# hw2_pcb.net
KiCad netlist of a schematic drawn in EAGLE
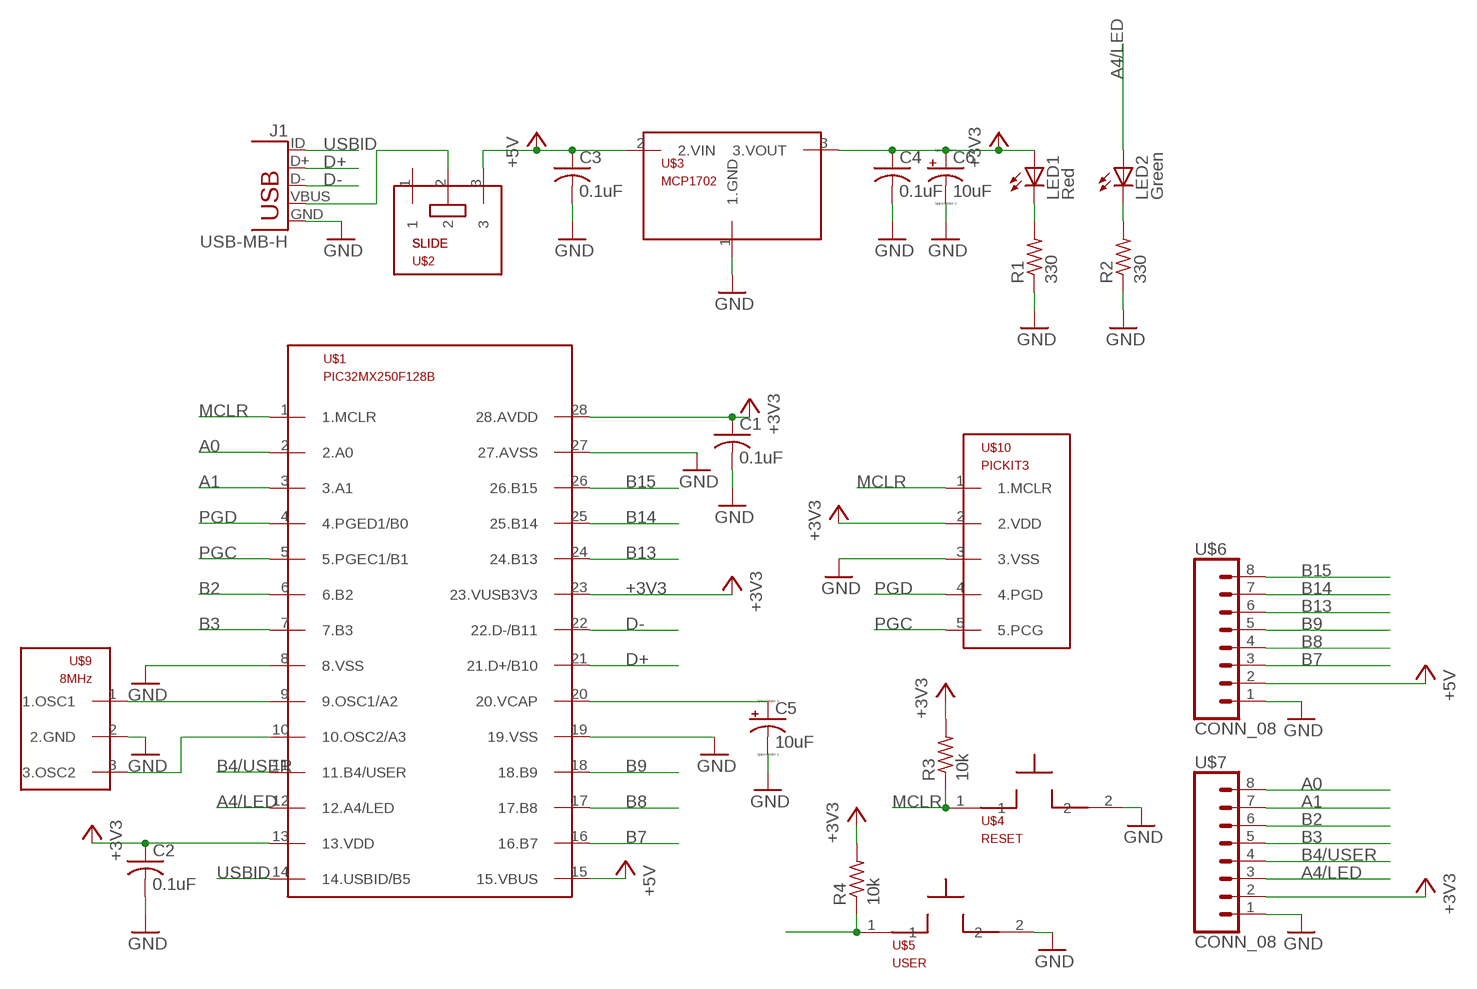
[diagram p0: schematic, sheet 1]

(export (version "E")
  (design (tool "Eeschema 10.0.6"))
  (components
    (comp (ref "C1")
      (value "0.1uF")
      (footprint "eagle-import:C025-025X050")
      (libsource (lib "eagle-import") (part "C-US025-025X050"))
    )
    (comp (ref "C2")
      (value "0.1uF")
      (footprint "eagle-import:C025-025X050")
      (libsource (lib "eagle-import") (part "C-US025-025X050"))
    )
    (comp (ref "C3")
      (value "0.1uF")
      (footprint "eagle-import:C025-025X050")
      (libsource (lib "eagle-import") (part "C-US025-025X050"))
    )
    (comp (ref "C4")
      (value "0.1uF")
      (footprint "eagle-import:C025-025X050")
      (libsource (lib "eagle-import") (part "C-US025-025X050"))
    )
    (comp (ref "C5")
      (value "10uF")
      (footprint "eagle-import:B45181B")
      (libsource (lib "eagle-import") (part "CPOL-USB45181B"))
    )
    (comp (ref "C6")
      (value "10uF")
      (footprint "eagle-import:B45181B")
      (libsource (lib "eagle-import") (part "CPOL-USB45181B"))
    )
    (comp (ref "J1")
      (value "USB-MB-H")
      (footprint "eagle-import:USB-MB-H")
      (libsource (lib "eagle-import") (part "USB-MB-H"))
    )
    (comp (ref "LED1")
      (value "Red")
      (footprint "eagle-import:LED3MM")
      (libsource (lib "eagle-import") (part "LED3MM"))
    )
    (comp (ref "LED2")
      (value "Green")
      (footprint "eagle-import:LED3MM")
      (libsource (lib "eagle-import") (part "LED3MM"))
    )
    (comp (ref "R1")
      (value "330")
      (footprint "eagle-import:0207_10")
      (libsource (lib "eagle-import") (part "R-US_0207/10"))
    )
    (comp (ref "R2")
      (value "330")
      (footprint "eagle-import:0207_10")
      (libsource (lib "eagle-import") (part "R-US_0207/10"))
    )
    (comp (ref "R3")
      (value "10k")
      (footprint "eagle-import:0207_10")
      (libsource (lib "eagle-import") (part "R-US_0207/10"))
    )
    (comp (ref "R4")
      (value "10k")
      (footprint "eagle-import:0207_10")
      (libsource (lib "eagle-import") (part "R-US_0207/10"))
    )
    (comp (ref "U$1")
      (value "PIC32MX250F128B")
      (footprint "eagle-import:DIL28-3")
      (libsource (lib "eagle-import") (part "PIC32MX250F128B"))
    )
    (comp (ref "U$2")
      (value "SLIDE")
      (footprint "eagle-import:SLIDE")
      (libsource (lib "eagle-import") (part "SLIDE"))
    )
    (comp (ref "U$3")
      (value "MCP1702")
      (footprint "eagle-import:TO92")
      (libsource (lib "eagle-import") (part "MCP1702"))
    )
    (comp (ref "U$4")
      (value "RESET")
      (footprint "eagle-import:PB")
      (libsource (lib "eagle-import") (part "PB"))
    )
    (comp (ref "U$5")
      (value "USER")
      (footprint "eagle-import:PB")
      (libsource (lib "eagle-import") (part "PB"))
    )
    (comp (ref "U$6")
      (value "CONN_08")
      (footprint "eagle-import:1X08")
      (libsource (lib "eagle-import") (part "CONN_08"))
    )
    (comp (ref "U$7")
      (value "CONN_08")
      (footprint "eagle-import:1X08")
      (libsource (lib "eagle-import") (part "CONN_08"))
    )
    (comp (ref "U$9")
      (value "8MHz")
      (footprint "eagle-import:OSC")
      (libsource (lib "eagle-import") (part "OSC"))
    )
    (comp (ref "U$10")
      (value "PICKIT3")
      (footprint "eagle-import:1X05")
      (libsource (lib "eagle-import") (part "PICKIT3"))
    )
  )
  (nets
    (net (code "1") (name "+3V3") (class "Default")
      (node (ref "C1") (pin "1") (pinfunction "1_1") (pintype "passive"))
      (node (ref "C2") (pin "1") (pinfunction "1_1") (pintype "passive"))
      (node (ref "C4") (pin "1") (pinfunction "1_1") (pintype "passive"))
      (node (ref "C6") (pin "+") (pinfunction "+_+") (pintype "passive"))
      (node (ref "LED1") (pin "A") (pinfunction "A_A") (pintype "passive"))
      (node (ref "R3") (pin "2") (pinfunction "2_2") (pintype "passive"))
      (node (ref "R4") (pin "2") (pinfunction "2_2") (pintype "passive"))
      (node (ref "U$1") (pin "13") (pinfunction "13.VDD_13") (pintype "bidirectional"))
      (node (ref "U$1") (pin "23") (pinfunction "23.VUSB3V3_23") (pintype "bidirectional"))
      (node (ref "U$1") (pin "28") (pinfunction "28.AVDD_28") (pintype "bidirectional"))
      (node (ref "U$10") (pin "2") (pinfunction "2.VDD_2") (pintype "bidirectional"))
      (node (ref "U$3") (pin "3") (pinfunction "3.VOUT_3") (pintype "bidirectional"))
      (node (ref "U$7") (pin "2") (pinfunction "2_2") (pintype "passive"))
    )
    (net (code "2") (name "+5V") (class "Default")
      (node (ref "C3") (pin "1") (pinfunction "1_1") (pintype "passive"))
      (node (ref "U$1") (pin "15") (pinfunction "15.VBUS_15") (pintype "bidirectional"))
      (node (ref "U$2") (pin "3") (pinfunction "3_3") (pintype "bidirectional"))
      (node (ref "U$3") (pin "2") (pinfunction "2.VIN_2") (pintype "bidirectional"))
      (node (ref "U$6") (pin "2") (pinfunction "2_2") (pintype "passive"))
    )
    (net (code "3") (name "/A0") (class "Default")
      (node (ref "U$1") (pin "2") (pinfunction "2.A0_2") (pintype "bidirectional"))
      (node (ref "U$7") (pin "8") (pinfunction "8_8") (pintype "passive"))
    )
    (net (code "4") (name "/A1") (class "Default")
      (node (ref "U$1") (pin "3") (pinfunction "3.A1_3") (pintype "bidirectional"))
      (node (ref "U$7") (pin "7") (pinfunction "7_7") (pintype "passive"))
    )
    (net (code "5") (name "/A4{slash}LED") (class "Default")
      (node (ref "LED2") (pin "A") (pinfunction "A_A") (pintype "passive"))
      (node (ref "U$1") (pin "12") (pinfunction "12.A4/LED_12") (pintype "bidirectional"))
      (node (ref "U$7") (pin "3") (pinfunction "3_3") (pintype "passive"))
    )
    (net (code "6") (name "/B2") (class "Default")
      (node (ref "U$1") (pin "6") (pinfunction "6.B2_6") (pintype "bidirectional"))
      (node (ref "U$7") (pin "6") (pinfunction "6_6") (pintype "passive"))
    )
    (net (code "7") (name "/B3") (class "Default")
      (node (ref "U$1") (pin "7") (pinfunction "7.B3_7") (pintype "bidirectional"))
      (node (ref "U$7") (pin "5") (pinfunction "5_5") (pintype "passive"))
    )
    (net (code "8") (name "/B4{slash}USER") (class "Default")
      (node (ref "R4") (pin "1") (pinfunction "1_1") (pintype "passive"))
      (node (ref "U$1") (pin "11") (pinfunction "11.B4/USER_11") (pintype "bidirectional"))
      (node (ref "U$5") (pin "1") (pinfunction "1_1") (pintype "bidirectional"))
      (node (ref "U$7") (pin "4") (pinfunction "4_4") (pintype "passive"))
    )
    (net (code "9") (name "/B7") (class "Default")
      (node (ref "U$1") (pin "16") (pinfunction "16.B7_16") (pintype "bidirectional"))
      (node (ref "U$6") (pin "3") (pinfunction "3_3") (pintype "passive"))
    )
    (net (code "10") (name "/B8") (class "Default")
      (node (ref "U$1") (pin "17") (pinfunction "17.B8_17") (pintype "bidirectional"))
      (node (ref "U$6") (pin "4") (pinfunction "4_4") (pintype "passive"))
    )
    (net (code "11") (name "/B9") (class "Default")
      (node (ref "U$1") (pin "18") (pinfunction "18.B9_18") (pintype "bidirectional"))
      (node (ref "U$6") (pin "5") (pinfunction "5_5") (pintype "passive"))
    )
    (net (code "12") (name "/B13") (class "Default")
      (node (ref "U$1") (pin "24") (pinfunction "24.B13_24") (pintype "bidirectional"))
      (node (ref "U$6") (pin "6") (pinfunction "6_6") (pintype "passive"))
    )
    (net (code "13") (name "/B14") (class "Default")
      (node (ref "U$1") (pin "25") (pinfunction "25.B14_25") (pintype "bidirectional"))
      (node (ref "U$6") (pin "7") (pinfunction "7_7") (pintype "passive"))
    )
    (net (code "14") (name "/B15") (class "Default")
      (node (ref "U$1") (pin "26") (pinfunction "26.B15_26") (pintype "bidirectional"))
      (node (ref "U$6") (pin "8") (pinfunction "8_8") (pintype "passive"))
    )
    (net (code "15") (name "/D+") (class "Default")
      (node (ref "J1") (pin "D+") (pinfunction "D+_D+") (pintype "bidirectional"))
      (node (ref "U$1") (pin "21") (pinfunction "21.D+/B10_21") (pintype "bidirectional"))
    )
    (net (code "16") (name "/D-") (class "Default")
      (node (ref "J1") (pin "D-") (pinfunction "D-_D-") (pintype "bidirectional"))
      (node (ref "U$1") (pin "22") (pinfunction "22.D-/B11_22") (pintype "bidirectional"))
    )
    (net (code "17") (name "/MCLR") (class "Default")
      (node (ref "R3") (pin "1") (pinfunction "1_1") (pintype "passive"))
      (node (ref "U$1") (pin "1") (pinfunction "1.MCLR_1") (pintype "bidirectional"))
      (node (ref "U$10") (pin "1") (pinfunction "1.MCLR_1") (pintype "bidirectional"))
      (node (ref "U$4") (pin "1") (pinfunction "1_1") (pintype "bidirectional"))
    )
    (net (code "18") (name "/PGC") (class "Default")
      (node (ref "U$1") (pin "5") (pinfunction "5.PGEC1/B1_5") (pintype "bidirectional"))
      (node (ref "U$10") (pin "5") (pinfunction "5.PCG_5") (pintype "bidirectional"))
    )
    (net (code "19") (name "/PGD") (class "Default")
      (node (ref "U$1") (pin "4") (pinfunction "4.PGED1/B0_4") (pintype "bidirectional"))
      (node (ref "U$10") (pin "4") (pinfunction "4.PGD_4") (pintype "bidirectional"))
    )
    (net (code "20") (name "/USBID") (class "Default")
      (node (ref "J1") (pin "ID") (pinfunction "ID_ID") (pintype "bidirectional"))
      (node (ref "U$1") (pin "14") (pinfunction "14.USBID/B5_14") (pintype "bidirectional"))
    )
    (net (code "21") (name "GND") (class "Default")
      (node (ref "C1") (pin "2") (pinfunction "2_2") (pintype "passive"))
      (node (ref "C2") (pin "2") (pinfunction "2_2") (pintype "passive"))
      (node (ref "C3") (pin "2") (pinfunction "2_2") (pintype "passive"))
      (node (ref "C4") (pin "2") (pinfunction "2_2") (pintype "passive"))
      (node (ref "C5") (pin "-") (pinfunction "-_-") (pintype "passive"))
      (node (ref "C6") (pin "-") (pinfunction "-_-") (pintype "passive"))
      (node (ref "J1") (pin "GND") (pinfunction "GND_GND") (pintype "bidirectional"))
      (node (ref "R1") (pin "1") (pinfunction "1_1") (pintype "passive"))
      (node (ref "R2") (pin "1") (pinfunction "1_1") (pintype "passive"))
      (node (ref "U$1") (pin "19") (pinfunction "19.VSS_19") (pintype "bidirectional"))
      (node (ref "U$1") (pin "27") (pinfunction "27.AVSS_27") (pintype "bidirectional"))
      (node (ref "U$1") (pin "8") (pinfunction "8.VSS_8") (pintype "bidirectional"))
      (node (ref "U$10") (pin "3") (pinfunction "3.VSS_3") (pintype "bidirectional"))
      (node (ref "U$3") (pin "1") (pinfunction "1.GND_1") (pintype "bidirectional"))
      (node (ref "U$4") (pin "2") (pinfunction "2_2") (pintype "bidirectional"))
      (node (ref "U$5") (pin "2") (pinfunction "2_2") (pintype "bidirectional"))
      (node (ref "U$6") (pin "1") (pinfunction "1_1") (pintype "passive"))
      (node (ref "U$7") (pin "1") (pinfunction "1_1") (pintype "passive"))
      (node (ref "U$9") (pin "2") (pinfunction "2.GND_2") (pintype "bidirectional"))
    )
    (net (code "22") (name "Net-(J1-PadVBUS)") (class "Default")
      (node (ref "J1") (pin "VBUS") (pinfunction "VBUS_VBUS") (pintype "bidirectional"))
      (node (ref "U$2") (pin "2") (pinfunction "2_2") (pintype "bidirectional"))
    )
    (net (code "23") (name "Net-(LED1-C)") (class "Default")
      (node (ref "LED1") (pin "K") (pinfunction "C_K") (pintype "passive"))
      (node (ref "R1") (pin "2") (pinfunction "2_2") (pintype "passive"))
    )
    (net (code "24") (name "Net-(LED2-C)") (class "Default")
      (node (ref "LED2") (pin "K") (pinfunction "C_K") (pintype "passive"))
      (node (ref "R2") (pin "2") (pinfunction "2_2") (pintype "passive"))
    )
    (net (code "25") (name "Net-(U$1-9.OSC1{slash}A2)") (class "Default")
      (node (ref "U$1") (pin "9") (pinfunction "9.OSC1/A2_9") (pintype "bidirectional"))
      (node (ref "U$9") (pin "1") (pinfunction "1.OSC1_1") (pintype "bidirectional"))
    )
    (net (code "26") (name "Net-(U$1-10.OSC2{slash}A3)") (class "Default")
      (node (ref "U$1") (pin "10") (pinfunction "10.OSC2/A3_10") (pintype "bidirectional"))
      (node (ref "U$9") (pin "3") (pinfunction "3.OSC2_3") (pintype "bidirectional"))
    )
    (net (code "27") (name "Net-(U$1-20.VCAP)") (class "Default")
      (node (ref "C5") (pin "+") (pinfunction "+_+") (pintype "passive"))
      (node (ref "U$1") (pin "20") (pinfunction "20.VCAP_20") (pintype "bidirectional"))
    )
    (net (code "28") (name "unconnected-(U$2-Pad1)") (class "Default")
      (node (ref "U$2") (pin "1") (pinfunction "1_1") (pintype "bidirectional"))
    )
  )
)
